# arduino_board_2iter.net
KiCad netlist of a schematic drawn in EAGLE
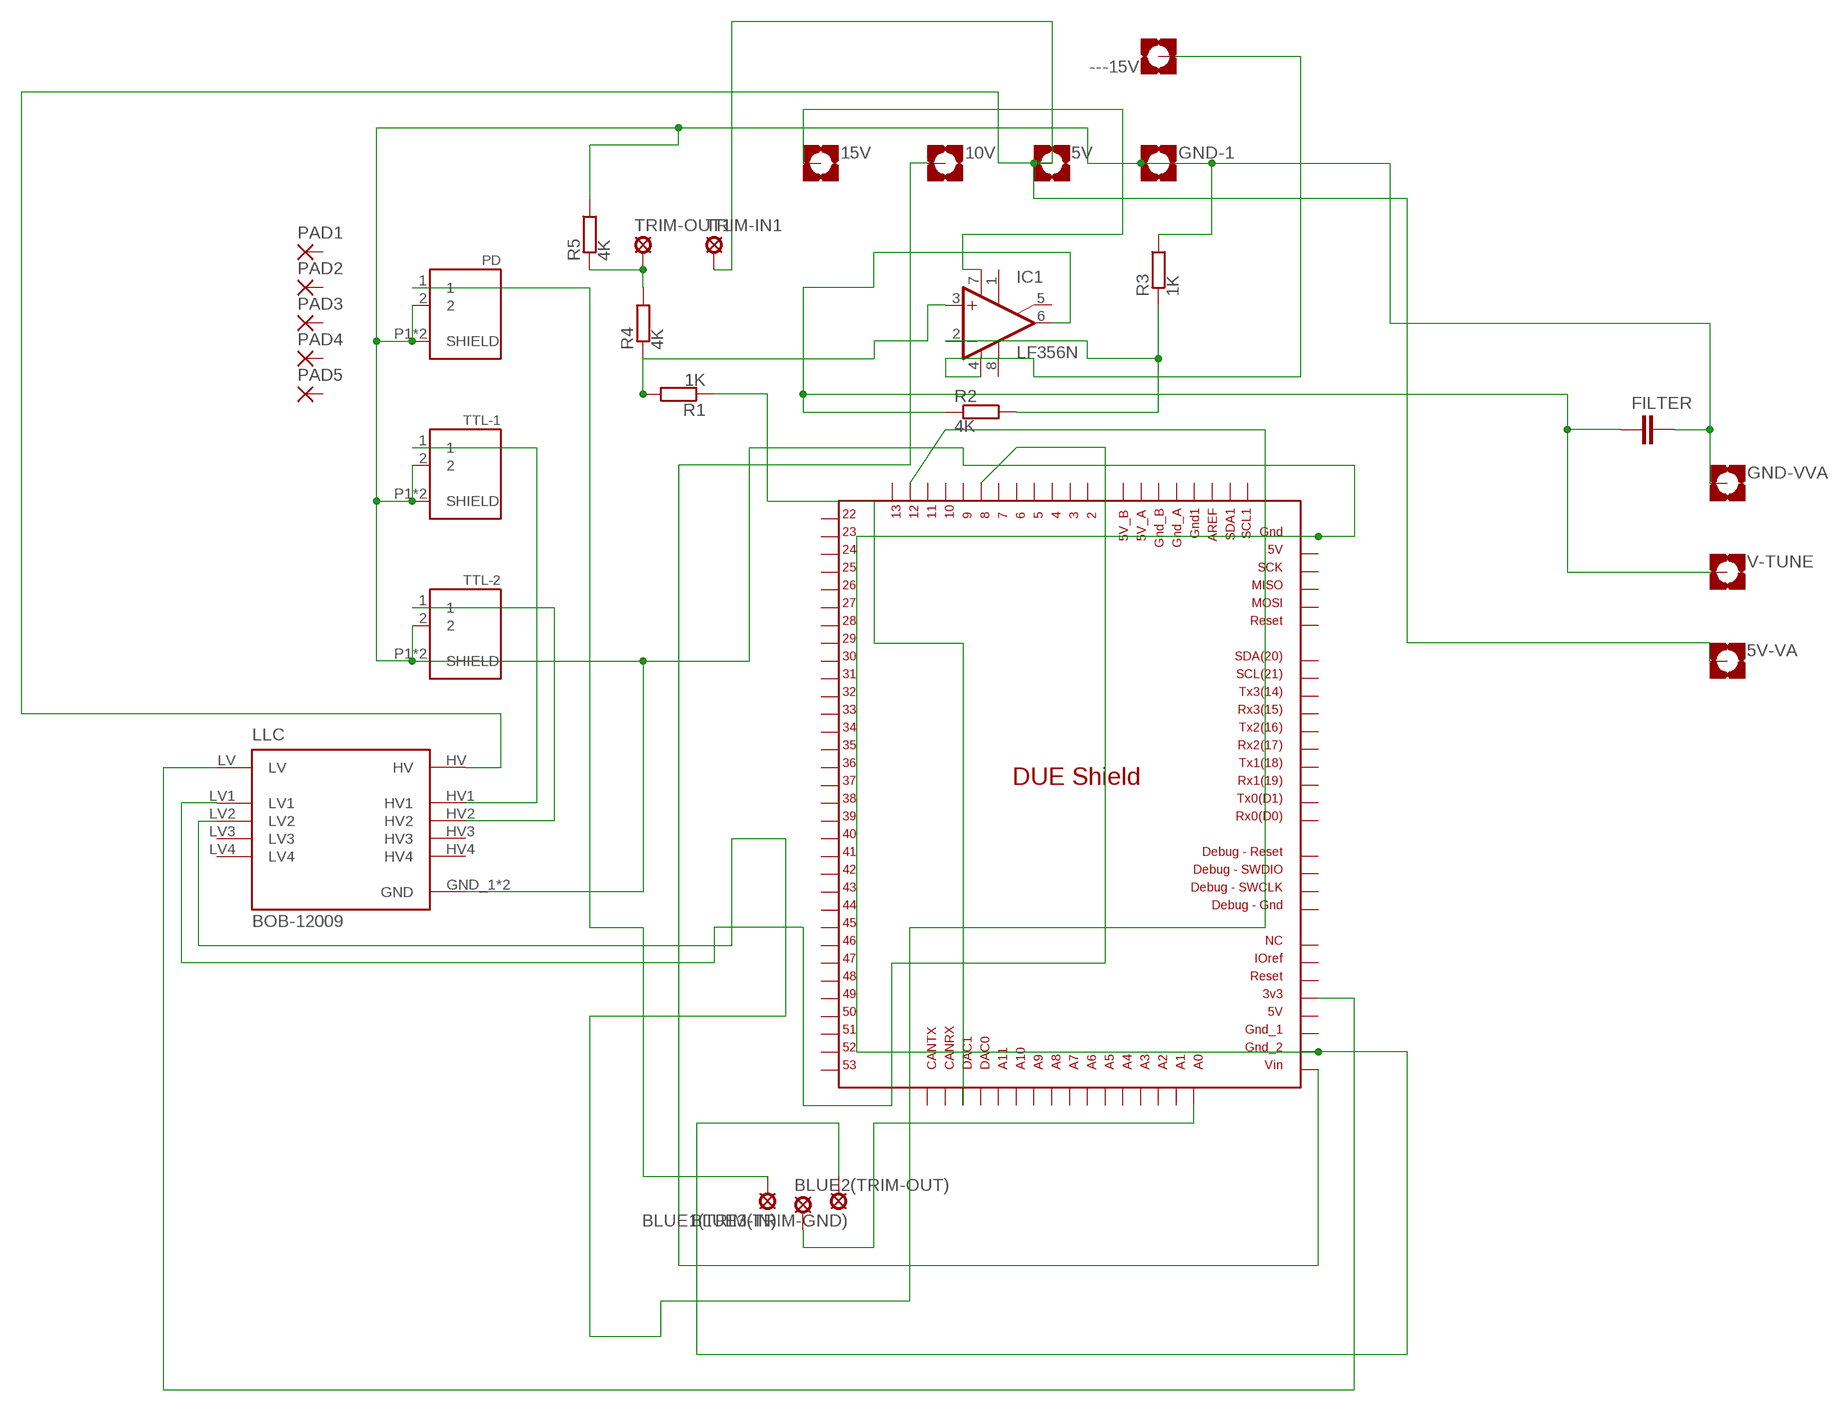
[diagram p0: schematic, sheet 1]

(export (version "E")
  (design (tool "Eeschema 10.0.6"))
  (components
    (comp (ref "---15V")
      (value "MOUNT-PAD-SQUARE2.8")
      (footprint "eagle-import:2,8-PAD-SQUARE")
      (libsource (lib "eagle-import") (part "MOUNT-PAD-SQUARE2.8"))
    )
    (comp (ref "5V")
      (value "MOUNT-PAD-SQUARE2.8")
      (footprint "eagle-import:2,8-PAD-SQUARE")
      (libsource (lib "eagle-import") (part "MOUNT-PAD-SQUARE2.8"))
    )
    (comp (ref "5V-VA")
      (value "MOUNT-PAD-SQUARE2.8")
      (footprint "eagle-import:2,8-PAD-SQUARE")
      (libsource (lib "eagle-import") (part "MOUNT-PAD-SQUARE2.8"))
    )
    (comp (ref "10V")
      (value "MOUNT-PAD-SQUARE2.8")
      (footprint "eagle-import:2,8-PAD-SQUARE")
      (libsource (lib "eagle-import") (part "MOUNT-PAD-SQUARE2.8"))
    )
    (comp (ref "15V")
      (value "MOUNT-PAD-SQUARE2.8")
      (footprint "eagle-import:2,8-PAD-SQUARE")
      (libsource (lib "eagle-import") (part "MOUNT-PAD-SQUARE2.8"))
    )
    (comp (ref "BLUE1(TRIM-IN)")
      (value "LSP10")
      (footprint "eagle-import:LSP10")
      (libsource (lib "eagle-import") (part "LSP10"))
    )
    (comp (ref "BLUE2(TRIM-OUT)")
      (value "LSP10")
      (footprint "eagle-import:LSP10")
      (libsource (lib "eagle-import") (part "LSP10"))
    )
    (comp (ref "BLUE3(TRIM-GND)")
      (value "LSP10")
      (footprint "eagle-import:LSP10")
      (libsource (lib "eagle-import") (part "LSP10"))
    )
    (comp (ref "FILTER")
      (value "C-EUC1812K")
      (footprint "eagle-import:C1812K")
      (libsource (lib "eagle-import") (part "C-EUC1812K"))
    )
    (comp (ref "GND-1")
      (value "MOUNT-PAD-SQUARE2.8")
      (footprint "eagle-import:2,8-PAD-SQUARE")
      (libsource (lib "eagle-import") (part "MOUNT-PAD-SQUARE2.8"))
    )
    (comp (ref "GND-VVA")
      (value "MOUNT-PAD-SQUARE2.8")
      (footprint "eagle-import:2,8-PAD-SQUARE")
      (libsource (lib "eagle-import") (part "MOUNT-PAD-SQUARE2.8"))
    )
    (comp (ref "IC1")
      (value "LF356N")
      (footprint "eagle-import:DIL08")
      (libsource (lib "eagle-import") (part "LF356N"))
    )
    (comp (ref "LLC")
      (value "BOB-12009")
      (footprint "eagle-import:CONV_BOB-12009")
      (fields (field (name "MF") "SparkFun"))
      (libsource (lib "eagle-import") (part "BOB-12009"))
    )
    (comp (ref "PAD1")
      (value "1,6/0,9")
      (footprint "eagle-import:1,6_0,9")
      (libsource (lib "eagle-import") (part "1,6/0,9"))
    )
    (comp (ref "PAD2")
      (value "1,6/0,9")
      (footprint "eagle-import:1,6_0,9")
      (libsource (lib "eagle-import") (part "1,6/0,9"))
    )
    (comp (ref "PAD3")
      (value "1,6/0,9")
      (footprint "eagle-import:1,6_0,9")
      (libsource (lib "eagle-import") (part "1,6/0,9"))
    )
    (comp (ref "PAD4")
      (value "1,6/0,9")
      (footprint "eagle-import:1,6_0,9")
      (libsource (lib "eagle-import") (part "1,6/0,9"))
    )
    (comp (ref "PAD5")
      (value "1,6/0,9")
      (footprint "eagle-import:1,6_0,9")
      (libsource (lib "eagle-import") (part "1,6/0,9"))
    )
    (comp (ref "PD")
      (value "1-1337543-0")
      (footprint "eagle-import:CONN_1-1337543-0")
      (fields (field (name "DIGI-KEY_PART_NUMBER") "A97553-ND") (field (name "MF") "TE Connectivity"))
      (libsource (lib "eagle-import") (part "1-1337543-0"))
    )
    (comp (ref "R1")
      (value "1K")
      (footprint "eagle-import:SMS-0")
      (libsource (lib "eagle-import") (part "SMS-0"))
    )
    (comp (ref "R2")
      (value "4K")
      (footprint "eagle-import:SMS-0")
      (libsource (lib "eagle-import") (part "SMS-0"))
    )
    (comp (ref "R3")
      (value "1K")
      (footprint "eagle-import:SMS-0")
      (libsource (lib "eagle-import") (part "SMS-0"))
    )
    (comp (ref "R4")
      (value "4K")
      (footprint "eagle-import:SMS-0")
      (libsource (lib "eagle-import") (part "SMS-0"))
    )
    (comp (ref "R5")
      (value "4K")
      (footprint "eagle-import:SMS-0")
      (libsource (lib "eagle-import") (part "SMS-0"))
    )
    (comp (ref "TRIM-IN1")
      (value "LSP10")
      (footprint "eagle-import:LSP10")
      (libsource (lib "eagle-import") (part "LSP10"))
    )
    (comp (ref "TRIM-OUT1")
      (value "LSP10")
      (footprint "eagle-import:LSP10")
      (libsource (lib "eagle-import") (part "LSP10"))
    )
    (comp (ref "TTL-1")
      (value "1-1337543-0")
      (footprint "eagle-import:CONN_1-1337543-0")
      (fields (field (name "DIGI-KEY_PART_NUMBER") "A97553-ND") (field (name "MF") "TE Connectivity"))
      (libsource (lib "eagle-import") (part "1-1337543-0"))
    )
    (comp (ref "TTL-2")
      (value "1-1337543-0")
      (footprint "eagle-import:CONN_1-1337543-0")
      (fields (field (name "DIGI-KEY_PART_NUMBER") "A97553-ND") (field (name "MF") "TE Connectivity"))
      (libsource (lib "eagle-import") (part "1-1337543-0"))
    )
    (comp (ref "U$1")
      (value "DUE(NORMAL)")
      (footprint "eagle-import:DUE(NORMAL)")
      (libsource (lib "eagle-import") (part "DUE(NORMAL)"))
    )
    (comp (ref "V-TUNE")
      (value "MOUNT-PAD-SQUARE2.8")
      (footprint "eagle-import:2,8-PAD-SQUARE")
      (libsource (lib "eagle-import") (part "MOUNT-PAD-SQUARE2.8"))
    )
  )
  (nets
    (net (code "1") (name "Net-(---15V-MOUNT)") (class "Default")
      (node (ref "---15V") (pin "B2,8") (pinfunction "MOUNT_B2,8") (pintype "passive"))
      (node (ref "IC1") (pin "4") (pinfunction "V-_4") (pintype "power_in"))
    )
    (net (code "2") (name "Net-(5V-MOUNT)") (class "Default")
      (node (ref "5V") (pin "B2,8") (pinfunction "MOUNT_B2,8") (pintype "passive"))
      (node (ref "5V-VA") (pin "B2,8") (pinfunction "MOUNT_B2,8") (pintype "passive"))
      (node (ref "LLC") (pin "HV") (pinfunction "HV_HV") (pintype "bidirectional"))
      (node (ref "TRIM-IN1") (pin "MP") (pinfunction "MP_MP") (pintype "passive"))
    )
    (net (code "3") (name "Net-(10V-MOUNT)") (class "Default")
      (node (ref "10V") (pin "B2,8") (pinfunction "MOUNT_B2,8") (pintype "passive"))
      (node (ref "U$1") (pin "VIN") (pinfunction "VIN_VIN") (pintype "bidirectional"))
    )
    (net (code "4") (name "Net-(15V-MOUNT)") (class "Default")
      (node (ref "15V") (pin "B2,8") (pinfunction "MOUNT_B2,8") (pintype "passive"))
      (node (ref "IC1") (pin "7") (pinfunction "V+_7") (pintype "power_in"))
    )
    (net (code "5") (name "Net-(BLUE1(TRIM-IN)-PadMP)") (class "Default")
      (node (ref "BLUE1(TRIM-IN)") (pin "MP") (pinfunction "MP_MP") (pintype "passive"))
      (node (ref "PD") (pin "1") (pinfunction "1_1") (pintype "passive"))
    )
    (net (code "6") (name "Net-(BLUE2(TRIM-OUT)-PadMP)") (class "Default")
      (node (ref "BLUE2(TRIM-OUT)") (pin "MP") (pinfunction "MP_MP") (pintype "passive"))
      (node (ref "U$1") (pin "A0") (pinfunction "A0_A0") (pintype "bidirectional"))
    )
    (net (code "7") (name "Net-(GND-1-MOUNT)") (class "Default")
      (node (ref "BLUE3(TRIM-GND)") (pin "MP") (pinfunction "MP_MP") (pintype "passive"))
      (node (ref "FILTER") (pin "2") (pinfunction "2_2") (pintype "passive"))
      (node (ref "GND-1") (pin "B2,8") (pinfunction "MOUNT_B2,8") (pintype "passive"))
      (node (ref "GND-VVA") (pin "B2,8") (pinfunction "MOUNT_B2,8") (pintype "passive"))
      (node (ref "LLC") (pin "GND_1") (pinfunction "GND_GND_1") (pintype "power_in"))
      (node (ref "LLC") (pin "GND_2") (pinfunction "GND_GND_2") (pintype "power_in"))
      (node (ref "PD") (pin "2") (pinfunction "2_2") (pintype "passive"))
      (node (ref "PD") (pin "P1") (pinfunction "SHIELD_P1") (pintype "passive"))
      (node (ref "PD") (pin "P2") (pinfunction "SHIELD_P2") (pintype "passive"))
      (node (ref "R3") (pin "1") (pinfunction "1_1") (pintype "passive"))
      (node (ref "R5") (pin "1") (pinfunction "1_1") (pintype "passive"))
      (node (ref "TTL-1") (pin "2") (pinfunction "2_2") (pintype "passive"))
      (node (ref "TTL-1") (pin "P1") (pinfunction "SHIELD_P1") (pintype "passive"))
      (node (ref "TTL-1") (pin "P2") (pinfunction "SHIELD_P2") (pintype "passive"))
      (node (ref "TTL-2") (pin "2") (pinfunction "2_2") (pintype "passive"))
      (node (ref "TTL-2") (pin "P1") (pinfunction "SHIELD_P1") (pintype "passive"))
      (node (ref "TTL-2") (pin "P2") (pinfunction "SHIELD_P2") (pintype "passive"))
      (node (ref "U$1") (pin "5V_ICSP") (pinfunction "5V_ICSP_5V_ICSP") (pintype "bidirectional"))
      (node (ref "U$1") (pin "GND_2") (pinfunction "GND_2_GND_2") (pintype "bidirectional"))
    )
    (net (code "8") (name "Net-(IC1-+IN)") (class "Default")
      (node (ref "IC1") (pin "3") (pinfunction "+IN_3") (pintype "input"))
      (node (ref "R1") (pin "1") (pinfunction "1_1") (pintype "passive"))
      (node (ref "R4") (pin "2") (pinfunction "2_2") (pintype "passive"))
    )
    (net (code "9") (name "Net-(IC1--IN)") (class "Default")
      (node (ref "IC1") (pin "2") (pinfunction "-IN_2") (pintype "input"))
      (node (ref "R2") (pin "1") (pinfunction "1_1") (pintype "passive"))
      (node (ref "R3") (pin "2") (pinfunction "2_2") (pintype "passive"))
    )
    (net (code "10") (name "Net-(IC1-OUT)") (class "Default")
      (node (ref "FILTER") (pin "1") (pinfunction "1_1") (pintype "passive"))
      (node (ref "IC1") (pin "6") (pinfunction "OUT_6") (pintype "output"))
      (node (ref "R2") (pin "2") (pinfunction "2_2") (pintype "passive"))
      (node (ref "V-TUNE") (pin "B2,8") (pinfunction "MOUNT_B2,8") (pintype "passive"))
    )
    (net (code "11") (name "Net-(LLC-PadHV1)") (class "Default")
      (node (ref "LLC") (pin "HV1") (pinfunction "HV1_HV1") (pintype "bidirectional"))
      (node (ref "TTL-1") (pin "1") (pinfunction "1_1") (pintype "passive"))
    )
    (net (code "12") (name "Net-(LLC-PadHV2)") (class "Default")
      (node (ref "LLC") (pin "HV2") (pinfunction "HV2_HV2") (pintype "bidirectional"))
      (node (ref "TTL-2") (pin "1") (pinfunction "1_1") (pintype "passive"))
    )
    (net (code "13") (name "Net-(LLC-PadLV)") (class "Default")
      (node (ref "LLC") (pin "LV") (pinfunction "LV_LV") (pintype "bidirectional"))
      (node (ref "U$1") (pin "3V3") (pinfunction "3V3_3V3") (pintype "bidirectional"))
    )
    (net (code "14") (name "Net-(LLC-PadLV1)") (class "Default")
      (node (ref "LLC") (pin "LV1") (pinfunction "LV1_LV1") (pintype "bidirectional"))
      (node (ref "U$1") (pin "8") (pinfunction "8_8") (pintype "bidirectional"))
    )
    (net (code "15") (name "Net-(LLC-PadLV2)") (class "Default")
      (node (ref "LLC") (pin "LV2") (pinfunction "LV2_LV2") (pintype "bidirectional"))
      (node (ref "U$1") (pin "12") (pinfunction "12_12") (pintype "bidirectional"))
    )
    (net (code "16") (name "Net-(R1-Pad2)") (class "Default")
      (node (ref "R1") (pin "2") (pinfunction "2_2") (pintype "passive"))
      (node (ref "U$1") (pin "DAC1") (pinfunction "DAC1_DAC1") (pintype "bidirectional"))
    )
    (net (code "17") (name "Net-(R4-Pad1)") (class "Default")
      (node (ref "R4") (pin "1") (pinfunction "1_1") (pintype "passive"))
      (node (ref "R5") (pin "2") (pinfunction "2_2") (pintype "passive"))
      (node (ref "TRIM-OUT1") (pin "MP") (pinfunction "MP_MP") (pintype "passive"))
    )
    (net (code "18") (name "unconnected-(IC1-ON1-Pad1)") (class "Default")
      (node (ref "IC1") (pin "1") (pinfunction "ON1_1") (pintype "passive"))
    )
    (net (code "19") (name "unconnected-(IC1-ON2-Pad5)") (class "Default")
      (node (ref "IC1") (pin "5") (pinfunction "ON2_5") (pintype "passive"))
    )
    (net (code "20") (name "unconnected-(IC1-OPT-Pad8)") (class "Default")
      (node (ref "IC1") (pin "8") (pinfunction "OPT_8") (pintype "passive"))
    )
    (net (code "21") (name "unconnected-(LLC-PadHV3)") (class "Default")
      (node (ref "LLC") (pin "HV3") (pinfunction "HV3_HV3") (pintype "bidirectional"))
    )
    (net (code "22") (name "unconnected-(LLC-PadHV4)") (class "Default")
      (node (ref "LLC") (pin "HV4") (pinfunction "HV4_HV4") (pintype "bidirectional"))
    )
    (net (code "23") (name "unconnected-(LLC-PadLV3)") (class "Default")
      (node (ref "LLC") (pin "LV3") (pinfunction "LV3_LV3") (pintype "bidirectional"))
    )
    (net (code "24") (name "unconnected-(LLC-PadLV4)") (class "Default")
      (node (ref "LLC") (pin "LV4") (pinfunction "LV4_LV4") (pintype "bidirectional"))
    )
    (net (code "25") (name "unconnected-(PAD1-P-Pad1)") (class "Default")
      (node (ref "PAD1") (pin "1") (pinfunction "P_1") (pintype "passive"))
    )
    (net (code "26") (name "unconnected-(PAD2-P-Pad1)") (class "Default")
      (node (ref "PAD2") (pin "1") (pinfunction "P_1") (pintype "passive"))
    )
    (net (code "27") (name "unconnected-(PAD3-P-Pad1)") (class "Default")
      (node (ref "PAD3") (pin "1") (pinfunction "P_1") (pintype "passive"))
    )
    (net (code "28") (name "unconnected-(PAD4-P-Pad1)") (class "Default")
      (node (ref "PAD4") (pin "1") (pinfunction "P_1") (pintype "passive"))
    )
    (net (code "29") (name "unconnected-(PAD5-P-Pad1)") (class "Default")
      (node (ref "PAD5") (pin "1") (pinfunction "P_1") (pintype "passive"))
    )
    (net (code "30") (name "unconnected-(U$1-Pad2)") (class "Default")
      (node (ref "U$1") (pin "2") (pinfunction "2_2") (pintype "bidirectional"))
    )
    (net (code "31") (name "unconnected-(U$1-Pad3)") (class "Default")
      (node (ref "U$1") (pin "3") (pinfunction "3_3") (pintype "bidirectional"))
    )
    (net (code "32") (name "unconnected-(U$1-Pad4)") (class "Default")
      (node (ref "U$1") (pin "4") (pinfunction "4_4") (pintype "bidirectional"))
    )
    (net (code "33") (name "unconnected-(U$1-Pad5)") (class "Default")
      (node (ref "U$1") (pin "5") (pinfunction "5_5") (pintype "bidirectional"))
    )
    (net (code "34") (name "unconnected-(U$1-Pad5V)") (class "Default")
      (node (ref "U$1") (pin "5V") (pinfunction "5V_5V") (pintype "bidirectional"))
    )
    (net (code "35") (name "unconnected-(U$1-Pad5V_A)") (class "Default")
      (node (ref "U$1") (pin "5V_A") (pinfunction "5V_A_5V_A") (pintype "bidirectional"))
    )
    (net (code "36") (name "unconnected-(U$1-Pad5V_B)") (class "Default")
      (node (ref "U$1") (pin "5V_B") (pinfunction "5V_B_5V_B") (pintype "bidirectional"))
    )
    (net (code "37") (name "unconnected-(U$1-Pad6)") (class "Default")
      (node (ref "U$1") (pin "6") (pinfunction "6_6") (pintype "bidirectional"))
    )
    (net (code "38") (name "unconnected-(U$1-Pad7)") (class "Default")
      (node (ref "U$1") (pin "7") (pinfunction "7_7") (pintype "bidirectional"))
    )
    (net (code "39") (name "unconnected-(U$1-Pad9)") (class "Default")
      (node (ref "U$1") (pin "9") (pinfunction "9_9") (pintype "bidirectional"))
    )
    (net (code "40") (name "unconnected-(U$1-Pad10)") (class "Default")
      (node (ref "U$1") (pin "10") (pinfunction "10_10") (pintype "bidirectional"))
    )
    (net (code "41") (name "unconnected-(U$1-Pad11)") (class "Default")
      (node (ref "U$1") (pin "11") (pinfunction "11_11") (pintype "bidirectional"))
    )
    (net (code "42") (name "unconnected-(U$1-Pad13)") (class "Default")
      (node (ref "U$1") (pin "13") (pinfunction "13_13") (pintype "bidirectional"))
    )
    (net (code "43") (name "unconnected-(U$1-Pad22)") (class "Default")
      (node (ref "U$1") (pin "22") (pinfunction "22_22") (pintype "bidirectional"))
    )
    (net (code "44") (name "unconnected-(U$1-Pad23)") (class "Default")
      (node (ref "U$1") (pin "23") (pinfunction "23_23") (pintype "bidirectional"))
    )
    (net (code "45") (name "unconnected-(U$1-Pad24)") (class "Default")
      (node (ref "U$1") (pin "24") (pinfunction "24_24") (pintype "bidirectional"))
    )
    (net (code "46") (name "unconnected-(U$1-Pad25)") (class "Default")
      (node (ref "U$1") (pin "25") (pinfunction "25_25") (pintype "bidirectional"))
    )
    (net (code "47") (name "unconnected-(U$1-Pad26)") (class "Default")
      (node (ref "U$1") (pin "26") (pinfunction "26_26") (pintype "bidirectional"))
    )
    (net (code "48") (name "unconnected-(U$1-Pad27)") (class "Default")
      (node (ref "U$1") (pin "27") (pinfunction "27_27") (pintype "bidirectional"))
    )
    (net (code "49") (name "unconnected-(U$1-Pad28)") (class "Default")
      (node (ref "U$1") (pin "28") (pinfunction "28_28") (pintype "bidirectional"))
    )
    (net (code "50") (name "unconnected-(U$1-Pad29)") (class "Default")
      (node (ref "U$1") (pin "29") (pinfunction "29_29") (pintype "bidirectional"))
    )
    (net (code "51") (name "unconnected-(U$1-Pad30)") (class "Default")
      (node (ref "U$1") (pin "30") (pinfunction "30_30") (pintype "bidirectional"))
    )
    (net (code "52") (name "unconnected-(U$1-Pad31)") (class "Default")
      (node (ref "U$1") (pin "31") (pinfunction "31_31") (pintype "bidirectional"))
    )
    (net (code "53") (name "unconnected-(U$1-Pad32)") (class "Default")
      (node (ref "U$1") (pin "32") (pinfunction "32_32") (pintype "bidirectional"))
    )
    (net (code "54") (name "unconnected-(U$1-Pad33)") (class "Default")
      (node (ref "U$1") (pin "33") (pinfunction "33_33") (pintype "bidirectional"))
    )
    (net (code "55") (name "unconnected-(U$1-Pad34)") (class "Default")
      (node (ref "U$1") (pin "34") (pinfunction "34_34") (pintype "bidirectional"))
    )
    (net (code "56") (name "unconnected-(U$1-Pad35)") (class "Default")
      (node (ref "U$1") (pin "35") (pinfunction "35_35") (pintype "bidirectional"))
    )
    (net (code "57") (name "unconnected-(U$1-Pad36)") (class "Default")
      (node (ref "U$1") (pin "36") (pinfunction "36_36") (pintype "bidirectional"))
    )
    (net (code "58") (name "unconnected-(U$1-Pad37)") (class "Default")
      (node (ref "U$1") (pin "37") (pinfunction "37_37") (pintype "bidirectional"))
    )
    (net (code "59") (name "unconnected-(U$1-Pad38)") (class "Default")
      (node (ref "U$1") (pin "38") (pinfunction "38_38") (pintype "bidirectional"))
    )
    (net (code "60") (name "unconnected-(U$1-Pad39)") (class "Default")
      (node (ref "U$1") (pin "39") (pinfunction "39_39") (pintype "bidirectional"))
    )
    (net (code "61") (name "unconnected-(U$1-Pad40)") (class "Default")
      (node (ref "U$1") (pin "40") (pinfunction "40_40") (pintype "bidirectional"))
    )
    (net (code "62") (name "unconnected-(U$1-Pad41)") (class "Default")
      (node (ref "U$1") (pin "41") (pinfunction "41_41") (pintype "bidirectional"))
    )
    (net (code "63") (name "unconnected-(U$1-Pad42)") (class "Default")
      (node (ref "U$1") (pin "42") (pinfunction "42_42") (pintype "bidirectional"))
    )
    (net (code "64") (name "unconnected-(U$1-Pad43)") (class "Default")
      (node (ref "U$1") (pin "43") (pinfunction "43_43") (pintype "bidirectional"))
    )
    (net (code "65") (name "unconnected-(U$1-Pad44)") (class "Default")
      (node (ref "U$1") (pin "44") (pinfunction "44_44") (pintype "bidirectional"))
    )
    (net (code "66") (name "unconnected-(U$1-Pad45)") (class "Default")
      (node (ref "U$1") (pin "45") (pinfunction "45_45") (pintype "bidirectional"))
    )
    (net (code "67") (name "unconnected-(U$1-Pad46)") (class "Default")
      (node (ref "U$1") (pin "46") (pinfunction "46_46") (pintype "bidirectional"))
    )
    (net (code "68") (name "unconnected-(U$1-Pad47)") (class "Default")
      (node (ref "U$1") (pin "47") (pinfunction "47_47") (pintype "bidirectional"))
    )
    (net (code "69") (name "unconnected-(U$1-Pad48)") (class "Default")
      (node (ref "U$1") (pin "48") (pinfunction "48_48") (pintype "bidirectional"))
    )
    (net (code "70") (name "unconnected-(U$1-Pad49)") (class "Default")
      (node (ref "U$1") (pin "49") (pinfunction "49_49") (pintype "bidirectional"))
    )
    (net (code "71") (name "unconnected-(U$1-Pad50)") (class "Default")
      (node (ref "U$1") (pin "50") (pinfunction "50_50") (pintype "bidirectional"))
    )
    (net (code "72") (name "unconnected-(U$1-Pad51)") (class "Default")
      (node (ref "U$1") (pin "51") (pinfunction "51_51") (pintype "bidirectional"))
    )
    (net (code "73") (name "unconnected-(U$1-Pad52)") (class "Default")
      (node (ref "U$1") (pin "52") (pinfunction "52_52") (pintype "bidirectional"))
    )
    (net (code "74") (name "unconnected-(U$1-Pad53)") (class "Default")
      (node (ref "U$1") (pin "53") (pinfunction "53_53") (pintype "bidirectional"))
    )
    (net (code "75") (name "unconnected-(U$1-PadA1)") (class "Default")
      (node (ref "U$1") (pin "A1") (pinfunction "A1_A1") (pintype "bidirectional"))
    )
    (net (code "76") (name "unconnected-(U$1-PadA2)") (class "Default")
      (node (ref "U$1") (pin "A2") (pinfunction "A2_A2") (pintype "bidirectional"))
    )
    (net (code "77") (name "unconnected-(U$1-PadA3)") (class "Default")
      (node (ref "U$1") (pin "A3") (pinfunction "A3_A3") (pintype "bidirectional"))
    )
    (net (code "78") (name "unconnected-(U$1-PadA4)") (class "Default")
      (node (ref "U$1") (pin "A4") (pinfunction "A4_A4") (pintype "bidirectional"))
    )
    (net (code "79") (name "unconnected-(U$1-PadA5)") (class "Default")
      (node (ref "U$1") (pin "A5") (pinfunction "A5_A5") (pintype "bidirectional"))
    )
    (net (code "80") (name "unconnected-(U$1-PadA6)") (class "Default")
      (node (ref "U$1") (pin "A6") (pinfunction "A6_A6") (pintype "bidirectional"))
    )
    (net (code "81") (name "unconnected-(U$1-PadA7)") (class "Default")
      (node (ref "U$1") (pin "A7") (pinfunction "A7_A7") (pintype "bidirectional"))
    )
    (net (code "82") (name "unconnected-(U$1-PadA8)") (class "Default")
      (node (ref "U$1") (pin "A8") (pinfunction "A8_A8") (pintype "bidirectional"))
    )
    (net (code "83") (name "unconnected-(U$1-PadA9)") (class "Default")
      (node (ref "U$1") (pin "A9") (pinfunction "A9_A9") (pintype "bidirectional"))
    )
    (net (code "84") (name "unconnected-(U$1-PadA10)") (class "Default")
      (node (ref "U$1") (pin "A10") (pinfunction "A10_A10") (pintype "bidirectional"))
    )
    (net (code "85") (name "unconnected-(U$1-PadA11)") (class "Default")
      (node (ref "U$1") (pin "A11") (pinfunction "A11_A11") (pintype "bidirectional"))
    )
    (net (code "86") (name "unconnected-(U$1-PadAREF)") (class "Default")
      (node (ref "U$1") (pin "AREF") (pinfunction "AREF_AREF") (pintype "bidirectional"))
    )
    (net (code "87") (name "unconnected-(U$1-PadCANRX)") (class "Default")
      (node (ref "U$1") (pin "CANRX") (pinfunction "CANRX_CANRX") (pintype "bidirectional"))
    )
    (net (code "88") (name "unconnected-(U$1-PadCANTX)") (class "Default")
      (node (ref "U$1") (pin "CANTX") (pinfunction "CANTX_CANTX") (pintype "bidirectional"))
    )
    (net (code "89") (name "unconnected-(U$1-PadDAC0)") (class "Default")
      (node (ref "U$1") (pin "DAC0") (pinfunction "DAC0_DAC0") (pintype "bidirectional"))
    )
    (net (code "90") (name "unconnected-(U$1-PadGND1)") (class "Default")
      (node (ref "U$1") (pin "GND1") (pinfunction "GND1_GND1") (pintype "bidirectional"))
    )
    (net (code "91") (name "unconnected-(U$1-PadGND_1)") (class "Default")
      (node (ref "U$1") (pin "GND_1") (pinfunction "GND_1_GND_1") (pintype "bidirectional"))
    )
    (net (code "92") (name "unconnected-(U$1-PadGND_A)") (class "Default")
      (node (ref "U$1") (pin "GND_A") (pinfunction "GND_A_GND_A") (pintype "bidirectional"))
    )
    (net (code "93") (name "unconnected-(U$1-PadGND_B)") (class "Default")
      (node (ref "U$1") (pin "GND_B") (pinfunction "GND_B_GND_B") (pintype "bidirectional"))
    )
    (net (code "94") (name "unconnected-(U$1-PadGND_DEBUG)") (class "Default")
      (node (ref "U$1") (pin "GND_DEBUG") (pinfunction "GND_DEBUG_GND_DEBUG") (pintype "bidirectional"))
    )
    (net (code "95") (name "unconnected-(U$1-PadGND_ICSP)") (class "Default")
      (node (ref "U$1") (pin "GND_ICSP") (pinfunction "GND_ICSP_GND_ICSP") (pintype "bidirectional"))
    )
    (net (code "96") (name "unconnected-(U$1-PadIOREF)") (class "Default")
      (node (ref "U$1") (pin "IOREF") (pinfunction "IOREF_IOREF") (pintype "bidirectional"))
    )
    (net (code "97") (name "unconnected-(U$1-PadMISO_ICSP)") (class "Default")
      (node (ref "U$1") (pin "MISO_ICSP") (pinfunction "MISO_ICSP_MISO_ICSP") (pintype "bidirectional"))
    )
    (net (code "98") (name "unconnected-(U$1-PadMOSI_ICSP)") (class "Default")
      (node (ref "U$1") (pin "MOSI_ICSP") (pinfunction "MOSI_ICSP_MOSI_ICSP") (pintype "bidirectional"))
    )
    (net (code "99") (name "unconnected-(U$1-PadNC)") (class "Default")
      (node (ref "U$1") (pin "NC") (pinfunction "NC_NC") (pintype "bidirectional"))
    )
    (net (code "100") (name "unconnected-(U$1-PadRESET)") (class "Default")
      (node (ref "U$1") (pin "RESET") (pinfunction "RESET_RESET") (pintype "bidirectional"))
    )
    (net (code "101") (name "unconnected-(U$1-PadRESET_DEBUG)") (class "Default")
      (node (ref "U$1") (pin "RESET_DEBUG") (pinfunction "RESET_DEBUG_RESET_DEBUG") (pintype "bidirectional"))
    )
    (net (code "102") (name "unconnected-(U$1-PadRESET_ICSP)") (class "Default")
      (node (ref "U$1") (pin "RESET_ICSP") (pinfunction "RESET_ICSP_RESET_ICSP") (pintype "bidirectional"))
    )
    (net (code "103") (name "unconnected-(U$1-PadRX0)") (class "Default")
      (node (ref "U$1") (pin "RX0") (pinfunction "RX0_RX0") (pintype "bidirectional"))
    )
    (net (code "104") (name "unconnected-(U$1-PadRX1)") (class "Default")
      (node (ref "U$1") (pin "RX1") (pinfunction "RX1_RX1") (pintype "bidirectional"))
    )
    (net (code "105") (name "unconnected-(U$1-PadRX2)") (class "Default")
      (node (ref "U$1") (pin "RX2") (pinfunction "RX2_RX2") (pintype "bidirectional"))
    )
    (net (code "106") (name "unconnected-(U$1-PadRX3)") (class "Default")
      (node (ref "U$1") (pin "RX3") (pinfunction "RX3_RX3") (pintype "bidirectional"))
    )
    (net (code "107") (name "unconnected-(U$1-PadSCK_ICSP)") (class "Default")
      (node (ref "U$1") (pin "SCK_ICSP") (pinfunction "SCK_ICSP_SCK_ICSP") (pintype "bidirectional"))
    )
    (net (code "108") (name "unconnected-(U$1-PadSCL)") (class "Default")
      (node (ref "U$1") (pin "SCL") (pinfunction "SCL_SCL") (pintype "bidirectional"))
    )
    (net (code "109") (name "unconnected-(U$1-PadSCL1)") (class "Default")
      (node (ref "U$1") (pin "SCL1") (pinfunction "SCL1_SCL1") (pintype "bidirectional"))
    )
    (net (code "110") (name "unconnected-(U$1-PadSDA)") (class "Default")
      (node (ref "U$1") (pin "SDA") (pinfunction "SDA_SDA") (pintype "bidirectional"))
    )
    (net (code "111") (name "unconnected-(U$1-PadSDA1)") (class "Default")
      (node (ref "U$1") (pin "SDA1") (pinfunction "SDA1_SDA1") (pintype "bidirectional"))
    )
    (net (code "112") (name "unconnected-(U$1-PadSWCLK_DEBUG)") (class "Default")
      (node (ref "U$1") (pin "SWCLK_DEBUG") (pinfunction "SWCLK_DEBUG_SWCLK_DEBUG") (pintype "bidirectional"))
    )
    (net (code "113") (name "unconnected-(U$1-PadSWDIO_DEBUG)") (class "Default")
      (node (ref "U$1") (pin "SWDIO_DEBUG") (pinfunction "SWDIO_DEBUG_SWDIO_DEBUG") (pintype "bidirectional"))
    )
    (net (code "114") (name "unconnected-(U$1-PadTX0)") (class "Default")
      (node (ref "U$1") (pin "TX0") (pinfunction "TX0_TX0") (pintype "bidirectional"))
    )
    (net (code "115") (name "unconnected-(U$1-PadTX1)") (class "Default")
      (node (ref "U$1") (pin "TX1") (pinfunction "TX1_TX1") (pintype "bidirectional"))
    )
    (net (code "116") (name "unconnected-(U$1-PadTX2)") (class "Default")
      (node (ref "U$1") (pin "TX2") (pinfunction "TX2_TX2") (pintype "bidirectional"))
    )
    (net (code "117") (name "unconnected-(U$1-PadTX3)") (class "Default")
      (node (ref "U$1") (pin "TX3") (pinfunction "TX3_TX3") (pintype "bidirectional"))
    )
  )
)
